# CAP_RELEASE.net
KiCad netlist of a schematic drawn in Altium Designer
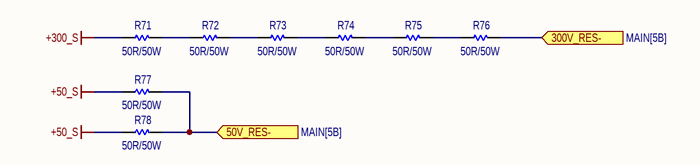
[diagram p0: CAP_RELEASE.SchDoc]

(export (version "E")
  (design (tool "Eeschema 10.0.6"))
  (components
    (comp (ref "R71")
      (value "50R/50W")
      (footprint "TO263-123")
      (description "TPAN0263F50R0K9")
      (fields
        (field (name "MANUFACTURER") "Generic Components")
        (field (name "PUBLISHER") "Altium Hobart Technology Centre")
      )
      (libsource (lib "Library") (part "Res-SMD"))
    )
    (comp (ref "R72")
      (value "50R/50W")
      (footprint "TO263-123")
      (description "TPAN0263F50R0K9")
      (fields
        (field (name "MANUFACTURER") "Generic Components")
        (field (name "PUBLISHER") "Altium Hobart Technology Centre")
      )
      (libsource (lib "Library") (part "Res-SMD"))
    )
    (comp (ref "R73")
      (value "50R/50W")
      (footprint "TO263-123")
      (description "TPAN0263F50R0K9")
      (fields
        (field (name "MANUFACTURER") "Generic Components")
        (field (name "PUBLISHER") "Altium Hobart Technology Centre")
      )
      (libsource (lib "Library") (part "Res-SMD"))
    )
    (comp (ref "R74")
      (value "50R/50W")
      (footprint "TO263-123")
      (description "TPAN0263F50R0K9")
      (fields
        (field (name "MANUFACTURER") "Generic Components")
        (field (name "PUBLISHER") "Altium Hobart Technology Centre")
      )
      (libsource (lib "Library") (part "Res-SMD"))
    )
    (comp (ref "R75")
      (value "50R/50W")
      (footprint "TO263-123")
      (description "TPAN0263F50R0K9")
      (fields
        (field (name "MANUFACTURER") "Generic Components")
        (field (name "PUBLISHER") "Altium Hobart Technology Centre")
      )
      (libsource (lib "Library") (part "Res-SMD"))
    )
    (comp (ref "R76")
      (value "50R/50W")
      (footprint "TO263-123")
      (description "TPAN0263F50R0K9")
      (fields
        (field (name "MANUFACTURER") "Generic Components")
        (field (name "PUBLISHER") "Altium Hobart Technology Centre")
      )
      (libsource (lib "Library") (part "Res-SMD"))
    )
    (comp (ref "R77")
      (value "50R/50W")
      (footprint "TO263-123")
      (description "TPAN0263F50R0K9")
      (fields
        (field (name "MANUFACTURER") "Generic Components")
        (field (name "PUBLISHER") "Altium Hobart Technology Centre")
      )
      (libsource (lib "Library") (part "Res-SMD"))
    )
    (comp (ref "R78")
      (value "50R/50W")
      (footprint "TO263-123")
      (description "TPAN0263F50R0K9")
      (fields
        (field (name "MANUFACTURER") "Generic Components")
        (field (name "PUBLISHER") "Altium Hobart Technology Centre")
      )
      (libsource (lib "Library") (part "Res-SMD"))
    )
  )
  (nets
    (net (code "1") (name "+50_S") (class "Default")
      (node (ref "R77") (pin "1") (pinfunction "1_1") (pintype "passive"))
      (node (ref "R78") (pin "1") (pinfunction "1_1") (pintype "passive"))
    )
    (net (code "2") (name "+300_S") (class "Default")
      (node (ref "R71") (pin "1") (pinfunction "1_1") (pintype "passive"))
    )
    (net (code "3") (name "/50V_RES-") (class "Default")
      (node (ref "R77") (pin "2") (pinfunction "2_2") (pintype "passive"))
      (node (ref "R78") (pin "2") (pinfunction "2_2") (pintype "passive"))
    )
    (net (code "4") (name "/300V_RES-") (class "Default")
      (node (ref "R76") (pin "2") (pinfunction "2_2") (pintype "passive"))
    )
    (net (code "5") (name "Net-(R71-Pad2)") (class "Default")
      (node (ref "R71") (pin "2") (pinfunction "2_2") (pintype "passive"))
      (node (ref "R72") (pin "1") (pinfunction "1_1") (pintype "passive"))
    )
    (net (code "6") (name "Net-(R72-Pad2)") (class "Default")
      (node (ref "R72") (pin "2") (pinfunction "2_2") (pintype "passive"))
      (node (ref "R73") (pin "1") (pinfunction "1_1") (pintype "passive"))
    )
    (net (code "7") (name "Net-(R73-Pad2)") (class "Default")
      (node (ref "R73") (pin "2") (pinfunction "2_2") (pintype "passive"))
      (node (ref "R74") (pin "1") (pinfunction "1_1") (pintype "passive"))
    )
    (net (code "8") (name "Net-(R74-Pad2)") (class "Default")
      (node (ref "R74") (pin "2") (pinfunction "2_2") (pintype "passive"))
      (node (ref "R75") (pin "1") (pinfunction "1_1") (pintype "passive"))
    )
    (net (code "9") (name "Net-(R75-Pad2)") (class "Default")
      (node (ref "R75") (pin "2") (pinfunction "2_2") (pintype "passive"))
      (node (ref "R76") (pin "1") (pinfunction "1_1") (pintype "passive"))
    )
  )
)
